# 3_3V_DIST.net
KiCad netlist of a schematic drawn in Altium Designer
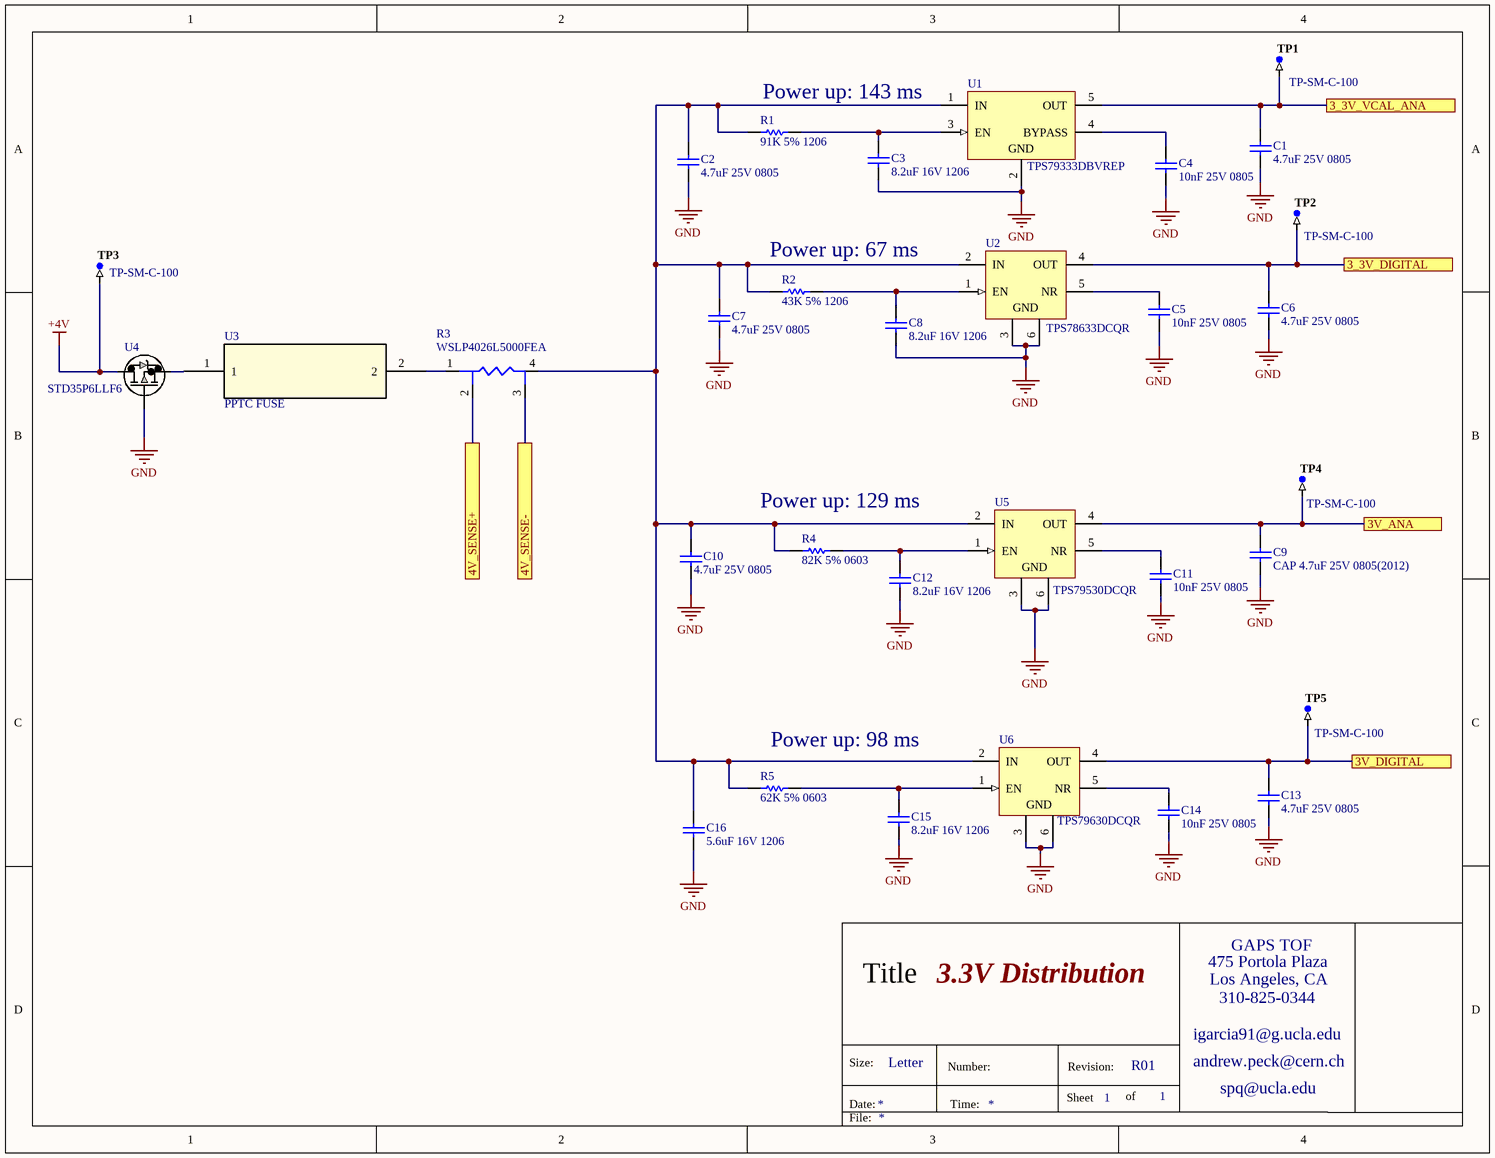
[diagram p0: 3_3V_DIST.SchDoc]

(export (version "E")
  (design (tool "Eeschema 10.0.6"))
  (components
    (comp (ref "C1")
      (value "4.7uF 25V 0805")
      (footprint "CAPC0805(2012)145_L")
      (description "CAP 4.7uF 25V ±10% 0805 (2012 Metric) Thickness 1.45mm SMD")
      (fields (field (name "TOLERANCE") "Â±10%"))
      (libsource (lib "Altium Content Vault") (part "CAP"))
    )
    (comp (ref "C2")
      (value "4.7uF 25V 0805")
      (footprint "CAPC0805(2012)145_L")
      (description "CAP 4.7uF 25V ±10% 0805 (2012 Metric) Thickness 1.45mm SMD")
      (fields (field (name "TOLERANCE") "Â±10%"))
      (libsource (lib "Altium Content Vault") (part "CAP"))
    )
    (comp (ref "C3")
      (value "8.2uF 16V 1206")
      (footprint "CAPC1206(3216)190_N")
      (description "CAP 8.2uF 16V ±20% 1206 (3216 Metric) Thickness 1.9mm SMD")
      (fields (field (name "TOLERANCE") "Â±20%"))
      (libsource (lib "Altium Content Vault") (part "CAP"))
    )
    (comp (ref "C4")
      (value "10nF 25V 0805")
      (footprint "CAPC0805(2012)145_M")
      (description "CAP 10nF 25V ±10% 0805 (2012 Metric) Thickness 1.45mm SMD")
      (fields (field (name "TOLERANCE") "Â±10%"))
      (libsource (lib "Altium Content Vault") (part "CAP"))
    )
    (comp (ref "C5")
      (value "10nF 25V 0805")
      (footprint "CAPC0805(2012)145_M")
      (description "CAP 10nF 25V ±10% 0805 (2012 Metric) Thickness 1.45mm SMD")
      (fields (field (name "TOLERANCE") "Â±10%"))
      (libsource (lib "Altium Content Vault") (part "CAP"))
    )
    (comp (ref "C6")
      (value "4.7uF 25V 0805")
      (footprint "CAPC0805(2012)145_L")
      (description "CAP 4.7uF 25V ±10% 0805 (2012 Metric) Thickness 1.45mm SMD")
      (fields (field (name "TOLERANCE") "Â±10%"))
      (libsource (lib "Altium Content Vault") (part "CAP"))
    )
    (comp (ref "C7")
      (value "4.7uF 25V 0805")
      (footprint "CAPC0805(2012)145_L")
      (description "CAP 4.7uF 25V ±10% 0805 (2012 Metric) Thickness 1.45mm SMD")
      (fields (field (name "TOLERANCE") "Â±10%"))
      (libsource (lib "Altium Content Vault") (part "CAP"))
    )
    (comp (ref "C8")
      (value "8.2uF 16V 1206")
      (footprint "CAPC1206(3216)190_N")
      (description "CAP 8.2uF 16V ±20% 1206 (3216 Metric) Thickness 1.9mm SMD")
      (fields (field (name "TOLERANCE") "Â±20%"))
      (libsource (lib "Altium Content Vault") (part "CAP"))
    )
    (comp (ref "C9")
      (value "CAP 4.7uF 25V 0805(2012)")
      (footprint "CAPC0805(2012)145_L")
      (description "CAP 4.7uF 25V ±10% 0805 (2012 Metric) Thickness 1.45mm SMD")
      (fields (field (name "TOLERANCE") "Â±10%"))
      (libsource (lib "Altium Content Vault") (part "CAP"))
    )
    (comp (ref "C10")
      (value "4.7uF 25V 0805")
      (footprint "CAPC0805(2012)145_L")
      (description "CAP 4.7uF 25V ±10% 0805 (2012 Metric) Thickness 1.45mm SMD")
      (fields (field (name "TOLERANCE") "Â±10%"))
      (libsource (lib "Altium Content Vault") (part "CAP"))
    )
    (comp (ref "C11")
      (value "10nF 25V 0805")
      (footprint "CAPC0805(2012)145_M")
      (description "CAP 10nF 25V ±10% 0805 (2012 Metric) Thickness 1.45mm SMD")
      (fields (field (name "TOLERANCE") "Â±10%"))
      (libsource (lib "Altium Content Vault") (part "CAP"))
    )
    (comp (ref "C12")
      (value "8.2uF 16V 1206")
      (footprint "CAPC1206(3216)190_N")
      (description "CAP 8.2uF 16V ±20% 1206 (3216 Metric) Thickness 1.9mm SMD")
      (fields (field (name "TOLERANCE") "Â±20%"))
      (libsource (lib "Altium Content Vault") (part "CAP"))
    )
    (comp (ref "C13")
      (value "4.7uF 25V 0805")
      (footprint "CAPC0805(2012)145_L")
      (description "CAP 4.7uF 25V ±10% 0805 (2012 Metric) Thickness 1.45mm SMD")
      (fields (field (name "TOLERANCE") "Â±10%"))
      (libsource (lib "Altium Content Vault") (part "CAP"))
    )
    (comp (ref "C14")
      (value "10nF 25V 0805")
      (footprint "CAPC0805(2012)145_M")
      (description "CAP 10nF 25V ±10% 0805 (2012 Metric) Thickness 1.45mm SMD")
      (fields (field (name "TOLERANCE") "Â±10%"))
      (libsource (lib "Altium Content Vault") (part "CAP"))
    )
    (comp (ref "C15")
      (value "8.2uF 16V 1206")
      (footprint "CAPC1206(3216)190_N")
      (description "CAP 8.2uF 16V ±20% 1206 (3216 Metric) Thickness 1.9mm SMD")
      (fields (field (name "TOLERANCE") "Â±20%"))
      (libsource (lib "Altium Content Vault") (part "CAP"))
    )
    (comp (ref "C16")
      (value "5.6uF 16V 1206")
      (footprint "CAPC1206(3216)190_N")
      (description "CAP 5.6uF 16V ±10% 1206 (3216 Metric) Thickness 1.9mm SMD")
      (fields (field (name "TOLERANCE") "Â±10%"))
      (libsource (lib "Altium Content Vault") (part "CAP"))
    )
    (comp (ref "R1")
      (value "91K 5% 1206")
      (footprint "RESC1206(3216)_M")
      (description "91K 0.25W 5% 1206 (3216 Metric)  SMD")
      (fields (field (name "TOLERANCE") "5 %") (field (name "POWER") "0.25 W"))
      (libsource (lib "Altium Content Vault") (part "RES"))
    )
    (comp (ref "R2")
      (value "43K 5% 1206")
      (footprint "RESC1206(3216)_N")
      (description "43K 0.25W 5% 1206 (3216 Metric)  SMD")
      (fields (field (name "TOLERANCE") "5 %") (field (name "POWER") "0.25 W"))
      (libsource (lib "Altium Content Vault") (part "RES"))
    )
    (comp (ref "R3")
      (value "WSLP4026L5000FEA")
      (description "Current Sense Resistors - SMD 7watt .0005ohm 1%")
      (libsource (lib "WSLP4026L5000FEA") (part "WSLP4026L5000FEA"))
    )
    (comp (ref "R4")
      (value "82K 5% 0603")
      (footprint "RESC0603(1608)_M")
      (description "82K 0.1W 5% 0603 (1608 Metric)  SMD")
      (fields (field (name "TOLERANCE") "5 %") (field (name "POWER") "0.1 W"))
      (libsource (lib "Altium Content Vault") (part "RES"))
    )
    (comp (ref "R5")
      (value "62K 5% 0603")
      (footprint "RESC0603(1608)_L")
      (description "62K 0.1W 5% 0603 (1608 Metric)  SMD")
      (fields (field (name "POWER") "0.1 W") (field (name "TOLERANCE") "5 %"))
      (libsource (lib "Altium Content Vault") (part "RES"))
    )
    (comp (ref "TP1")
      (value "TP-SM-C-100")
      (footprint "TP-SM-C-100")
      (description "Test Point, Surface Mount, Circular, Pad Diameter 1 mm")
      (fields (field (name "MANUFACTURER") "No Vendor"))
      (libsource (lib "Altium Content Vault") (part "TP-SM"))
    )
    (comp (ref "TP2")
      (value "TP-SM-C-100")
      (footprint "TP-SM-C-100")
      (description "Test Point, Surface Mount, Circular, Pad Diameter 1 mm")
      (fields (field (name "MANUFACTURER") "No Vendor"))
      (libsource (lib "Altium Content Vault") (part "TP-SM"))
    )
    (comp (ref "TP3")
      (value "TP-SM-C-100")
      (footprint "TP-SM-C-100")
      (description "Test Point, Surface Mount, Circular, Pad Diameter 1 mm")
      (fields (field (name "MANUFACTURER") "No Vendor"))
      (libsource (lib "Altium Content Vault") (part "TP-SM"))
    )
    (comp (ref "TP4")
      (value "TP-SM-C-100")
      (footprint "TP-SM-C-100")
      (description "Test Point, Surface Mount, Circular, Pad Diameter 1 mm")
      (fields (field (name "MANUFACTURER") "No Vendor"))
      (libsource (lib "Altium Content Vault") (part "TP-SM"))
    )
    (comp (ref "TP5")
      (value "TP-SM-C-100")
      (footprint "TP-SM-C-100")
      (description "Test Point, Surface Mount, Circular, Pad Diameter 1 mm")
      (fields (field (name "MANUFACTURER") "No Vendor"))
      (libsource (lib "Altium Content Vault") (part "TP-SM"))
    )
    (comp (ref "U1")
      (value "TPS79333DBVREP")
      (footprint "DBV0005A_M")
      (fields (field (name "MANUFACTURER") "Texas Instruments"))
      (libsource (lib "TPS79333DBVREP") (part "CMP-0394-00316-2"))
    )
    (comp (ref "U2")
      (value "TPS78633DCQR")
      (footprint "DCQ0006A_L")
      (fields (field (name "MANUFACTURER") "Texas Instruments"))
      (libsource (lib "TPS78633DCQR") (part "CMP-0395-00353-2"))
    )
    (comp (ref "U3")
      (value "PPTC FUSE")
      (footprint "0ZCF")
      (description "Resettable Fuses - PPTC")
      (fields (field (name "MANUFACTURER_PART_NUMBER") "0ZCF0250FF2C"))
      (libsource (lib "0ZCF0250FF2C") (part "0ZCF0250FF2C"))
    )
    (comp (ref "U4")
      (value "STD35P6LLF6")
      (footprint "DPAK")
      (description "MOSFET P-channel 60 V, 0.025 Ohm typ., 35 A STripFET F6 Power MOSFET in a DPAK package")
      (fields (field (name "MANUFACTURER_PART_NUMBER") "STD35NF06T4"))
      (libsource (lib "STD35P6LLF6") (part "STD35P6LLF6"))
    )
    (comp (ref "U5")
      (value "TPS79530DCQR")
      (footprint "DCQ0006A_L")
      (fields (field (name "MANUFACTURER") "Texas Instruments"))
      (libsource (lib "TPS79530DCQR") (part "CMP-0395-00302-2"))
    )
    (comp (ref "U6")
      (value "TPS79630DCQR")
      (footprint "DCQ0006A_L")
      (fields (field (name "MANUFACTURER") "Texas Instruments"))
      (libsource (lib "TPS79630DCQR") (part "CMP-0395-00336-2"))
    )
  )
  (nets
    (net (code "1") (name "+4V") (class "Default")
      (node (ref "TP3") (pin "1") (pinfunction "1_1") (pintype "input"))
      (node (ref "U4") (pin "2") (pinfunction "D_2") (pintype "passive"))
    )
    (net (code "2") (name "/3V_ANA") (class "Default")
      (node (ref "C9") (pin "2") (pinfunction "2_2") (pintype "passive"))
      (node (ref "TP4") (pin "1") (pinfunction "1_1") (pintype "input"))
      (node (ref "U5") (pin "4") (pinfunction "OUT_4") (pintype "power_in"))
    )
    (net (code "3") (name "/3V_DIGITAL") (class "Default")
      (node (ref "C13") (pin "2") (pinfunction "2_2") (pintype "passive"))
      (node (ref "TP5") (pin "1") (pinfunction "1_1") (pintype "input"))
      (node (ref "U6") (pin "4") (pinfunction "OUT_4") (pintype "power_in"))
    )
    (net (code "4") (name "/3_3V_DIGITAL") (class "Default")
      (node (ref "C6") (pin "2") (pinfunction "2_2") (pintype "passive"))
      (node (ref "TP2") (pin "1") (pinfunction "1_1") (pintype "input"))
      (node (ref "U2") (pin "4") (pinfunction "OUT_4") (pintype "power_in"))
    )
    (net (code "5") (name "/3_3V_VCAL_ANA") (class "Default")
      (node (ref "C1") (pin "2") (pinfunction "2_2") (pintype "passive"))
      (node (ref "TP1") (pin "1") (pinfunction "1_1") (pintype "input"))
      (node (ref "U1") (pin "5") (pinfunction "OUT_5") (pintype "power_in"))
    )
    (net (code "6") (name "/4V_SENSE+") (class "Default") (node (ref "R3") (pin "2") (pintype "passive")))
    (net (code "7") (name "/4V_SENSE-") (class "Default") (node (ref "R3") (pin "3") (pintype "passive")))
    (net (code "8") (name "GND") (class "Default")
      (node (ref "C1") (pin "1") (pinfunction "1_1") (pintype "passive"))
      (node (ref "C10") (pin "1") (pinfunction "1_1") (pintype "passive"))
      (node (ref "C11") (pin "1") (pinfunction "1_1") (pintype "passive"))
      (node (ref "C12") (pin "1") (pinfunction "1_1") (pintype "passive"))
      (node (ref "C13") (pin "1") (pinfunction "1_1") (pintype "passive"))
      (node (ref "C14") (pin "1") (pinfunction "1_1") (pintype "passive"))
      (node (ref "C15") (pin "1") (pinfunction "1_1") (pintype "passive"))
      (node (ref "C16") (pin "1") (pinfunction "1_1") (pintype "passive"))
      (node (ref "C2") (pin "1") (pinfunction "1_1") (pintype "passive"))
      (node (ref "C3") (pin "1") (pinfunction "1_1") (pintype "passive"))
      (node (ref "C4") (pin "1") (pinfunction "1_1") (pintype "passive"))
      (node (ref "C5") (pin "1") (pinfunction "1_1") (pintype "passive"))
      (node (ref "C6") (pin "1") (pinfunction "1_1") (pintype "passive"))
      (node (ref "C7") (pin "1") (pinfunction "1_1") (pintype "passive"))
      (node (ref "C8") (pin "1") (pinfunction "1_1") (pintype "passive"))
      (node (ref "C9") (pin "1") (pinfunction "1_1") (pintype "passive"))
      (node (ref "U1") (pin "2") (pinfunction "GND_2") (pintype "power_in"))
      (node (ref "U2") (pin "3") (pinfunction "GND_3") (pintype "power_in"))
      (node (ref "U2") (pin "6") (pinfunction "GND_6") (pintype "power_in"))
      (node (ref "U4") (pin "1") (pinfunction "G_1") (pintype "passive"))
      (node (ref "U5") (pin "3") (pinfunction "GND_3") (pintype "power_in"))
      (node (ref "U5") (pin "6") (pinfunction "GND_6") (pintype "power_in"))
      (node (ref "U6") (pin "3") (pinfunction "GND_3") (pintype "power_in"))
      (node (ref "U6") (pin "6") (pinfunction "GND_6") (pintype "power_in"))
    )
    (net (code "9") (name "Net-(R3-Pad1)") (class "Default")
      (node (ref "R3") (pin "1") (pintype "passive"))
      (node (ref "U3") (pin "2") (pinfunction "2_2") (pintype "passive"))
    )
    (net (code "10") (name "Net-(U1-BYPASS)") (class "Default")
      (node (ref "C4") (pin "2") (pinfunction "2_2") (pintype "passive"))
      (node (ref "U1") (pin "4") (pinfunction "BYPASS_4") (pintype "passive"))
    )
    (net (code "11") (name "Net-(U1-EN)") (class "Default")
      (node (ref "C3") (pin "2") (pinfunction "2_2") (pintype "passive"))
      (node (ref "R1") (pin "2") (pinfunction "2_2") (pintype "passive"))
      (node (ref "U1") (pin "3") (pinfunction "EN_3") (pintype "input"))
    )
    (net (code "12") (name "Net-(U1-IN)") (class "Default")
      (node (ref "C10") (pin "2") (pinfunction "2_2") (pintype "passive"))
      (node (ref "C16") (pin "2") (pinfunction "2_2") (pintype "passive"))
      (node (ref "C2") (pin "2") (pinfunction "2_2") (pintype "passive"))
      (node (ref "C7") (pin "2") (pinfunction "2_2") (pintype "passive"))
      (node (ref "R1") (pin "1") (pinfunction "1_1") (pintype "passive"))
      (node (ref "R2") (pin "1") (pinfunction "1_1") (pintype "passive"))
      (node (ref "R3") (pin "4") (pintype "passive"))
      (node (ref "R4") (pin "1") (pinfunction "1_1") (pintype "passive"))
      (node (ref "R5") (pin "1") (pinfunction "1_1") (pintype "passive"))
      (node (ref "U1") (pin "1") (pinfunction "IN_1") (pintype "power_in"))
      (node (ref "U2") (pin "2") (pinfunction "IN_2") (pintype "power_in"))
      (node (ref "U5") (pin "2") (pinfunction "IN_2") (pintype "power_in"))
      (node (ref "U6") (pin "2") (pinfunction "IN_2") (pintype "power_in"))
    )
    (net (code "13") (name "Net-(U2-EN)") (class "Default")
      (node (ref "C8") (pin "2") (pinfunction "2_2") (pintype "passive"))
      (node (ref "R2") (pin "2") (pinfunction "2_2") (pintype "passive"))
      (node (ref "U2") (pin "1") (pinfunction "EN_1") (pintype "input"))
    )
    (net (code "14") (name "Net-(U2-NR)") (class "Default")
      (node (ref "C5") (pin "2") (pinfunction "2_2") (pintype "passive"))
      (node (ref "U2") (pin "5") (pinfunction "NR_5") (pintype "passive"))
    )
    (net (code "15") (name "Net-(U4-S)") (class "Default")
      (node (ref "U3") (pin "1") (pinfunction "1_1") (pintype "passive"))
      (node (ref "U4") (pin "3") (pinfunction "S_3") (pintype "passive"))
    )
    (net (code "16") (name "Net-(U5-EN)") (class "Default")
      (node (ref "C12") (pin "2") (pinfunction "2_2") (pintype "passive"))
      (node (ref "R4") (pin "2") (pinfunction "2_2") (pintype "passive"))
      (node (ref "U5") (pin "1") (pinfunction "EN_1") (pintype "input"))
    )
    (net (code "17") (name "Net-(U5-NR)") (class "Default")
      (node (ref "C11") (pin "2") (pinfunction "2_2") (pintype "passive"))
      (node (ref "U5") (pin "5") (pinfunction "NR_5") (pintype "passive"))
    )
    (net (code "18") (name "Net-(U6-EN)") (class "Default")
      (node (ref "C15") (pin "2") (pinfunction "2_2") (pintype "passive"))
      (node (ref "R5") (pin "2") (pinfunction "2_2") (pintype "passive"))
      (node (ref "U6") (pin "1") (pinfunction "EN_1") (pintype "input"))
    )
    (net (code "19") (name "Net-(U6-NR)") (class "Default")
      (node (ref "C14") (pin "2") (pinfunction "2_2") (pintype "passive"))
      (node (ref "U6") (pin "5") (pinfunction "NR_5") (pintype "passive"))
    )
  )
)
